# 140709_AriloTX_REV2_1_0.net
KiCad netlist of a schematic drawn in EAGLE
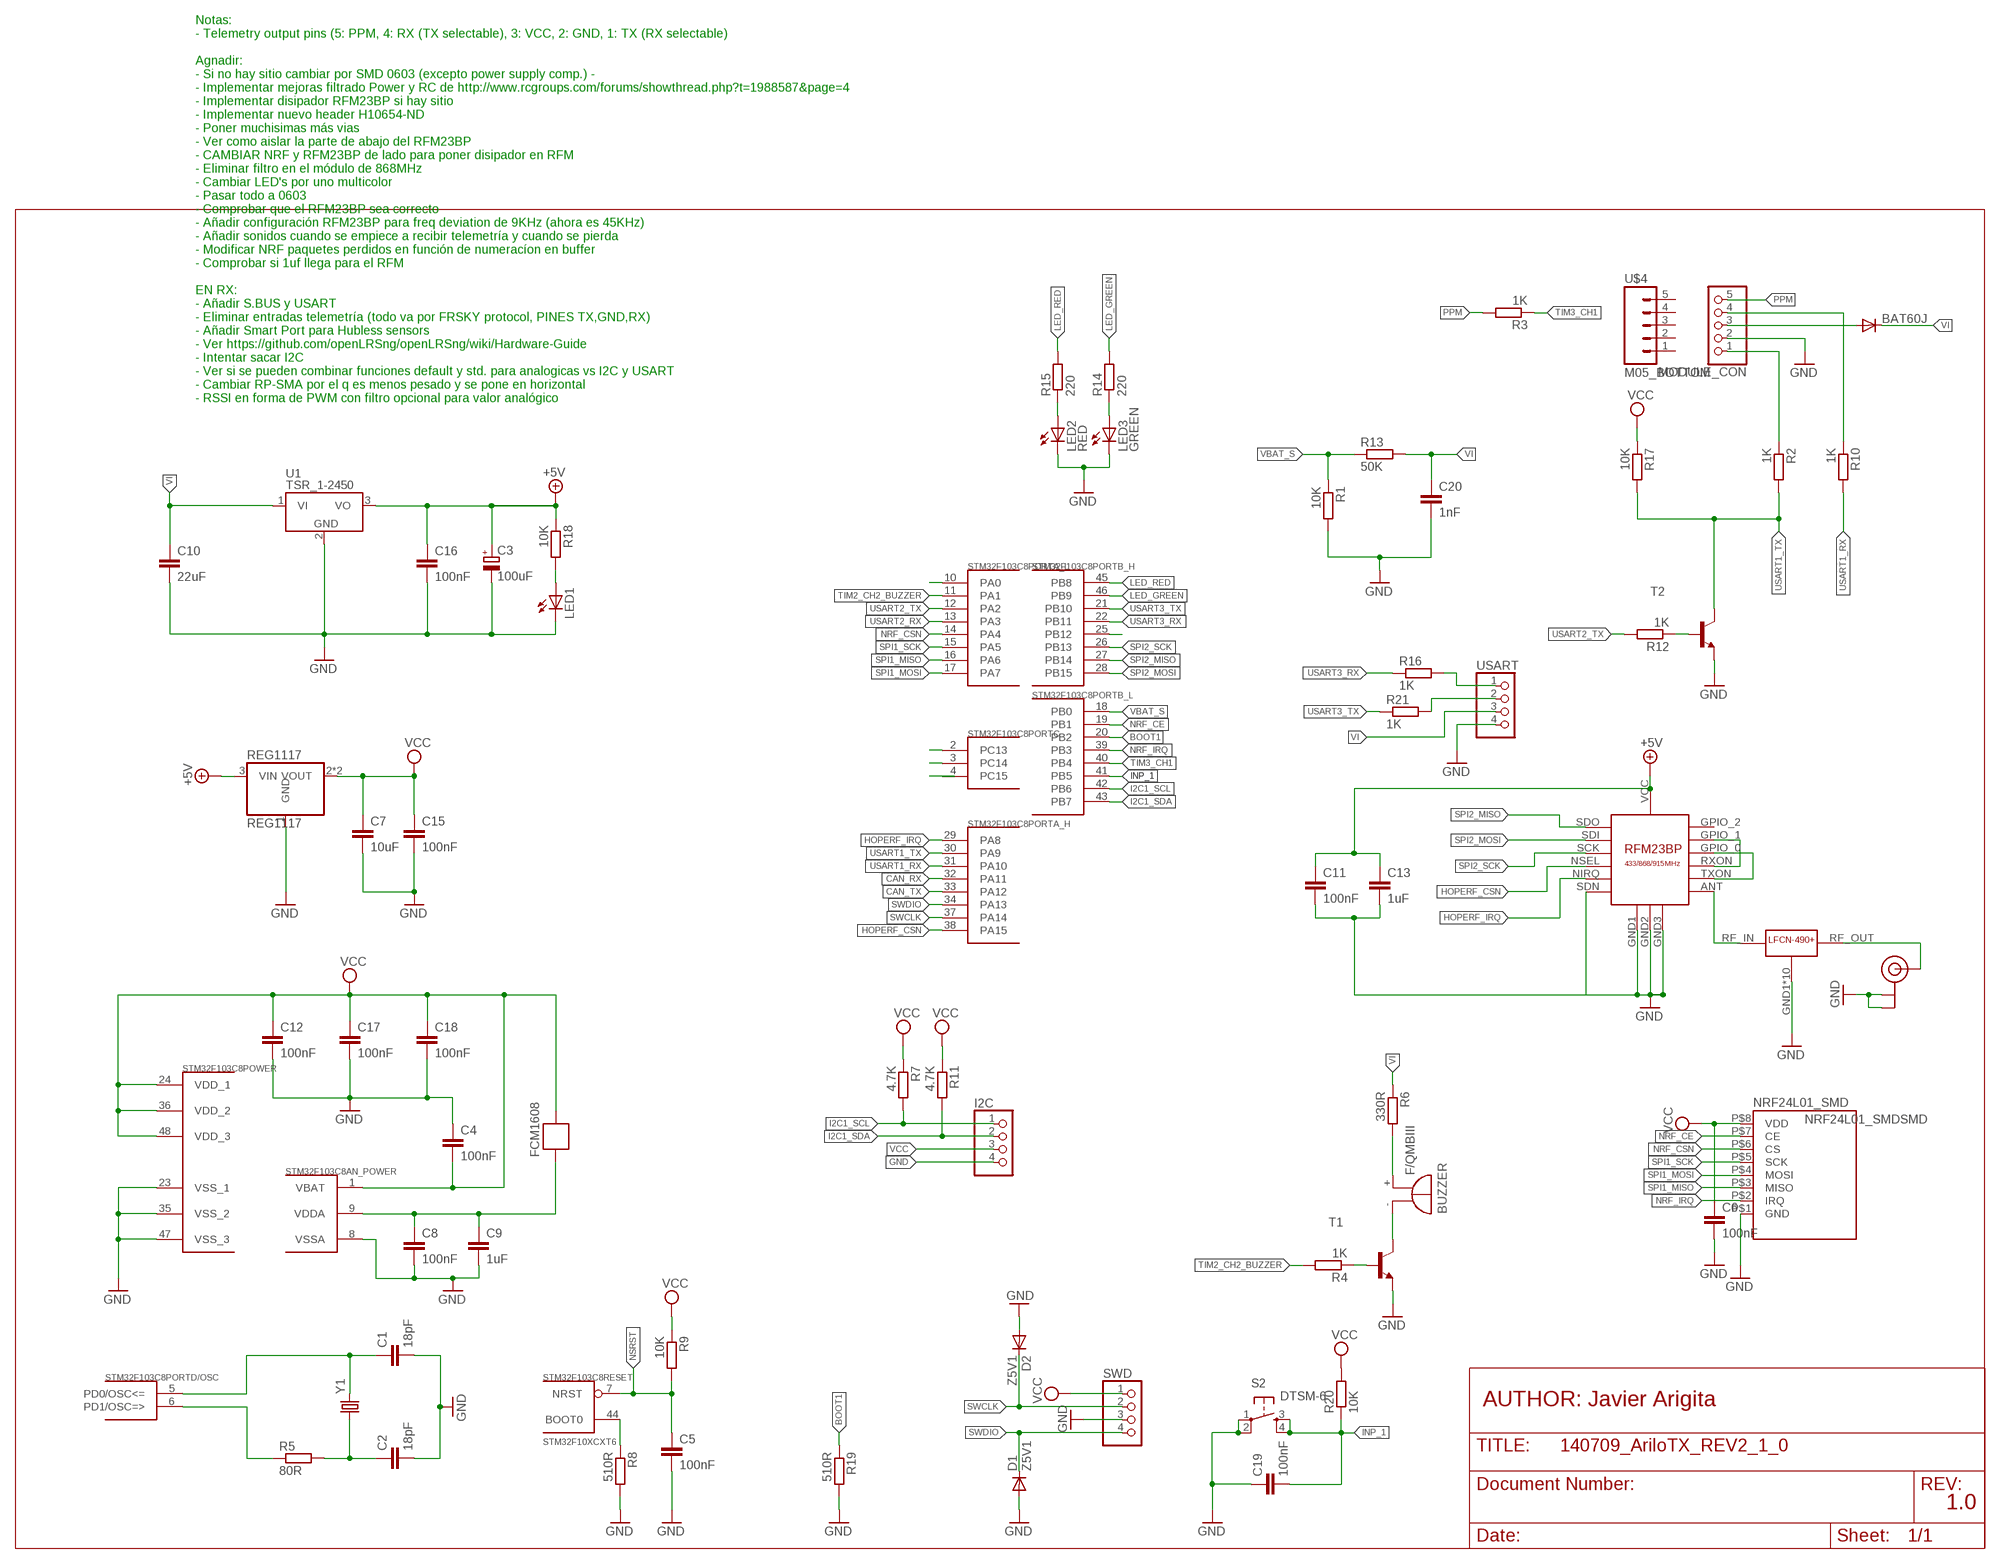
[diagram p0: schematic, sheet 1]

(export (version "E")
  (design (tool "Eeschema 10.0.6"))
  (components
    (comp (ref "BAT60J")
      (value "DIODE-SOD323-R")
      (footprint "eagle-import:SOD323-R")
      (libsource (lib "eagle-import") (part "DIODE-SOD323-R"))
    )
    (comp (ref "BUZZER")
      (value "F/QMBIII")
      (footprint "eagle-import:F_QMBIII")
      (libsource (lib "eagle-import") (part "F/QMBIII"))
    )
    (comp (ref "C1")
      (value "18pF")
      (footprint "eagle-import:C0603")
      (libsource (lib "eagle-import") (part "C-EUC0603"))
    )
    (comp (ref "C2")
      (value "18pF")
      (footprint "eagle-import:C0603")
      (libsource (lib "eagle-import") (part "C-EUC0603"))
    )
    (comp (ref "C3")
      (value "100uF")
      (footprint "eagle-import:SMC_B")
      (libsource (lib "eagle-import") (part "CPOL-EUSMCB"))
    )
    (comp (ref "C4")
      (value "100nF")
      (footprint "eagle-import:C0603")
      (libsource (lib "eagle-import") (part "C-EUC0603"))
    )
    (comp (ref "C5")
      (value "100nF")
      (footprint "eagle-import:C0603")
      (libsource (lib "eagle-import") (part "C-EUC0603"))
    )
    (comp (ref "C6")
      (value "100nF")
      (footprint "eagle-import:C0603")
      (libsource (lib "eagle-import") (part "C-EUC0603"))
    )
    (comp (ref "C7")
      (value "10uF")
      (footprint "eagle-import:C0805")
      (libsource (lib "eagle-import") (part "C-EUC0805"))
    )
    (comp (ref "C8")
      (value "100nF")
      (footprint "eagle-import:C0603")
      (libsource (lib "eagle-import") (part "C-EUC0603"))
    )
    (comp (ref "C9")
      (value "1uF")
      (footprint "eagle-import:C0603")
      (libsource (lib "eagle-import") (part "C-EUC0603"))
    )
    (comp (ref "C10")
      (value "22uF")
      (footprint "eagle-import:C3216")
      (libsource (lib "eagle-import") (part "resistor_C-EUC3216"))
    )
    (comp (ref "C11")
      (value "100nF")
      (footprint "eagle-import:C0603")
      (libsource (lib "eagle-import") (part "C-EUC0603"))
    )
    (comp (ref "C12")
      (value "100nF")
      (footprint "eagle-import:C0603")
      (libsource (lib "eagle-import") (part "C-EUC0603"))
    )
    (comp (ref "C13")
      (value "1uF")
      (footprint "eagle-import:C0603")
      (libsource (lib "eagle-import") (part "C-EUC0603"))
    )
    (comp (ref "C15")
      (value "100nF")
      (footprint "eagle-import:C0603")
      (libsource (lib "eagle-import") (part "C-EUC0603"))
    )
    (comp (ref "C16")
      (value "100nF")
      (footprint "eagle-import:C0603")
      (libsource (lib "eagle-import") (part "C-EUC0603"))
    )
    (comp (ref "C17")
      (value "100nF")
      (footprint "eagle-import:C0603")
      (libsource (lib "eagle-import") (part "C-EUC0603"))
    )
    (comp (ref "C18")
      (value "100nF")
      (footprint "eagle-import:C0603")
      (libsource (lib "eagle-import") (part "C-EUC0603"))
    )
    (comp (ref "C19")
      (value "100nF")
      (footprint "eagle-import:C0603")
      (libsource (lib "eagle-import") (part "C-EUC0603"))
    )
    (comp (ref "C20")
      (value "1nF")
      (footprint "eagle-import:C0603")
      (libsource (lib "eagle-import") (part "C-EUC0603"))
    )
    (comp (ref "D1")
      (value "Z5V1")
      (footprint "eagle-import:SOD323-R")
      (libsource (lib "eagle-import") (part "DIODE-SOD323-R"))
    )
    (comp (ref "D2")
      (value "Z5V1")
      (footprint "eagle-import:SOD323-R")
      (libsource (lib "eagle-import") (part "DIODE-SOD323-R"))
    )
    (comp (ref "FCM1608")
      (value "FERRITE-BEAD")
      (footprint "eagle-import:R0603")
      (libsource (lib "eagle-import") (part "FERRITE-BEAD"))
    )
    (comp (ref "I2C")
      (value "PINHD-1X4")
      (footprint "eagle-import:1X04")
      (libsource (lib "eagle-import") (part "PINHD-1X4"))
    )
    (comp (ref "LED1")
      (value "LEDCHIP-LED0603")
      (footprint "eagle-import:CHIP-LED0603")
      (libsource (lib "eagle-import") (part "LEDCHIP-LED0603"))
    )
    (comp (ref "LED2")
      (value "RED")
      (footprint "eagle-import:CHIP-LED0603")
      (libsource (lib "eagle-import") (part "LEDCHIP-LED0603"))
    )
    (comp (ref "LED3")
      (value "GREEN")
      (footprint "eagle-import:CHIP-LED0603")
      (libsource (lib "eagle-import") (part "LEDCHIP-LED0603"))
    )
    (comp (ref "MODULE_CON")
      (value "PINHD-1X5")
      (footprint "eagle-import:1X05")
      (libsource (lib "eagle-import") (part "PINHD-1X5"))
    )
    (comp (ref "NRF24L01_SMD")
      (value "NRF24L01_SMDSMD")
      (footprint "eagle-import:NRF24L01_SMD")
      (libsource (lib "eagle-import") (part "NRF24L01_SMDSMD"))
    )
    (comp (ref "R1")
      (value "10K")
      (footprint "eagle-import:R0603")
      (libsource (lib "eagle-import") (part "R-EU_R0603"))
    )
    (comp (ref "R2")
      (value "1K")
      (footprint "eagle-import:R0603")
      (libsource (lib "eagle-import") (part "R-EU_R0603"))
    )
    (comp (ref "R3")
      (value "1K")
      (footprint "eagle-import:R0603")
      (libsource (lib "eagle-import") (part "R-EU_R0603"))
    )
    (comp (ref "R4")
      (value "1K")
      (footprint "eagle-import:R0603")
      (libsource (lib "eagle-import") (part "R-EU_R0603"))
    )
    (comp (ref "R5")
      (value "80R")
      (footprint "eagle-import:R0603")
      (libsource (lib "eagle-import") (part "R-EU_R0603"))
    )
    (comp (ref "R6")
      (value "330R")
      (footprint "eagle-import:R0603")
      (libsource (lib "eagle-import") (part "R-EU_R0603"))
    )
    (comp (ref "R7")
      (value "4.7K")
      (footprint "eagle-import:R0603")
      (libsource (lib "eagle-import") (part "R-EU_R0603"))
    )
    (comp (ref "R8")
      (value "510R")
      (footprint "eagle-import:R0603")
      (libsource (lib "eagle-import") (part "R-EU_R0603"))
    )
    (comp (ref "R9")
      (value "10K")
      (footprint "eagle-import:R0603")
      (libsource (lib "eagle-import") (part "R-EU_R0603"))
    )
    (comp (ref "R10")
      (value "1K")
      (footprint "eagle-import:R0603")
      (libsource (lib "eagle-import") (part "R-EU_R0603"))
    )
    (comp (ref "R11")
      (value "4.7K")
      (footprint "eagle-import:R0603")
      (libsource (lib "eagle-import") (part "R-EU_R0603"))
    )
    (comp (ref "R12")
      (value "1K")
      (footprint "eagle-import:R0603")
      (libsource (lib "eagle-import") (part "R-EU_R0603"))
    )
    (comp (ref "R13")
      (value "50K")
      (footprint "eagle-import:R0603")
      (libsource (lib "eagle-import") (part "R-EU_R0603"))
    )
    (comp (ref "R14")
      (value "220")
      (footprint "eagle-import:R0603")
      (libsource (lib "eagle-import") (part "R-EU_R0603"))
    )
    (comp (ref "R15")
      (value "220")
      (footprint "eagle-import:R0603")
      (libsource (lib "eagle-import") (part "R-EU_R0603"))
    )
    (comp (ref "R16")
      (value "1K")
      (footprint "eagle-import:R0603")
      (libsource (lib "eagle-import") (part "R-EU_R0603"))
    )
    (comp (ref "R17")
      (value "10K")
      (footprint "eagle-import:R0603")
      (libsource (lib "eagle-import") (part "R-EU_R0603"))
    )
    (comp (ref "R18")
      (value "10K")
      (footprint "eagle-import:R0603")
      (libsource (lib "eagle-import") (part "R-EU_R0603"))
    )
    (comp (ref "R19")
      (value "510R")
      (footprint "eagle-import:R0603")
      (libsource (lib "eagle-import") (part "R-EU_R0603"))
    )
    (comp (ref "R20")
      (value "10K")
      (footprint "eagle-import:R0603")
      (libsource (lib "eagle-import") (part "R-EU_R0603"))
    )
    (comp (ref "R21")
      (value "1K")
      (footprint "eagle-import:R0603")
      (libsource (lib "eagle-import") (part "R-EU_R0603"))
    )
    (comp (ref "REG1117")
      (value "REG1117")
      (footprint "eagle-import:SOT223")
      (libsource (lib "eagle-import") (part "REG1117"))
    )
    (comp (ref "S2")
      (value "DTSM-6")
      (footprint "eagle-import:DTSM-6")
      (libsource (lib "eagle-import") (part "DTSM-6"))
    )
    (comp (ref "STM32F103C8")
      (value "STM32F10XCXT6")
      (footprint "eagle-import:TQFP48")
      (libsource (lib "eagle-import") (part "STM32F10XCXT6"))
    )
    (comp (ref "SWD")
      (value "PINHD-1X4")
      (footprint "eagle-import:1X04")
      (libsource (lib "eagle-import") (part "PINHD-1X4"))
    )
    (comp (ref "T1")
      (value "BC848-NPN-SOT23-BEC")
      (footprint "eagle-import:SOT23-BEC")
      (libsource (lib "eagle-import") (part "-NPN-SOT23-BECBC848"))
    )
    (comp (ref "T2")
      (value "BC848-NPN-SOT23-BEC")
      (footprint "eagle-import:SOT23-BEC")
      (libsource (lib "eagle-import") (part "-NPN-SOT23-BECBC848"))
    )
    (comp (ref "U$1")
      (value "RFM23BP")
      (footprint "eagle-import:RFM23BP")
      (libsource (lib "eagle-import") (part "RFM23BP"))
    )
    (comp (ref "U$2")
      (value "LFCN490+")
      (footprint "eagle-import:LFCN490+")
      (libsource (lib "eagle-import") (part "LFCN490+"))
    )
    (comp (ref "U$3")
      (value "U.FL")
      (footprint "eagle-import:U.FL")
      (libsource (lib "eagle-import") (part "U.FL"))
    )
    (comp (ref "U$4")
      (value "M05_BOTTOM")
      (footprint "eagle-import:M05_BOTTOM")
      (libsource (lib "eagle-import") (part "M05_BOTTOM"))
    )
    (comp (ref "U1")
      (value "TSR_1-2450")
      (footprint "eagle-import:TSR-1")
      (libsource (lib "eagle-import") (part "TSR_1-2450"))
    )
    (comp (ref "USART")
      (value "PINHD-1X4")
      (footprint "eagle-import:1X04")
      (libsource (lib "eagle-import") (part "PINHD-1X4"))
    )
    (comp (ref "Y1")
      (value "CRYSTAL5X3")
      (footprint "eagle-import:CRYSTAL-SMD-5X3")
      (libsource (lib "eagle-import") (part "CRYSTAL5X3"))
    )
  )
  (nets
    (net (code "1") (name "+5V") (class "Default")
      (node (ref "C11") (pin "1") (pinfunction "1_1") (pintype "passive"))
      (node (ref "C13") (pin "1") (pinfunction "1_1") (pintype "passive"))
      (node (ref "C16") (pin "1") (pinfunction "1_1") (pintype "passive"))
      (node (ref "C3") (pin "+") (pinfunction "+_+") (pintype "passive"))
      (node (ref "R18") (pin "1") (pinfunction "1_1") (pintype "passive"))
      (node (ref "REG1117") (pin "3") (pinfunction "VIN_3") (pintype "input"))
      (node (ref "U$1") (pin "VCC") (pinfunction "VCC_VCC") (pintype "power_in"))
      (node (ref "U1") (pin "3") (pinfunction "VO_3") (pintype "power_in"))
    )
    (net (code "2") (name "BOOT1") (class "Default")
      (node (ref "R19") (pin "1") (pinfunction "1_1") (pintype "passive"))
      (node (ref "STM32F103C8") (pin "20") (pinfunction "PB2_20") (pintype "bidirectional"))
    )
    (net (code "3") (name "CAN_RX") (class "Default")
      (node (ref "STM32F103C8") (pin "32") (pinfunction "PA11_32") (pintype "bidirectional"))
    )
    (net (code "4") (name "CAN_TX") (class "Default")
      (node (ref "STM32F103C8") (pin "33") (pinfunction "PA12_33") (pintype "bidirectional"))
    )
    (net (code "5") (name "GND") (class "Default")
      (node (ref "C1") (pin "2") (pinfunction "2_2") (pintype "passive"))
      (node (ref "C10") (pin "2") (pinfunction "2_2") (pintype "passive"))
      (node (ref "C11") (pin "2") (pinfunction "2_2") (pintype "passive"))
      (node (ref "C12") (pin "2") (pinfunction "2_2") (pintype "passive"))
      (node (ref "C13") (pin "2") (pinfunction "2_2") (pintype "passive"))
      (node (ref "C15") (pin "2") (pinfunction "2_2") (pintype "passive"))
      (node (ref "C16") (pin "2") (pinfunction "2_2") (pintype "passive"))
      (node (ref "C17") (pin "2") (pinfunction "2_2") (pintype "passive"))
      (node (ref "C18") (pin "2") (pinfunction "2_2") (pintype "passive"))
      (node (ref "C19") (pin "1") (pinfunction "1_1") (pintype "passive"))
      (node (ref "C2") (pin "2") (pinfunction "2_2") (pintype "passive"))
      (node (ref "C20") (pin "2") (pinfunction "2_2") (pintype "passive"))
      (node (ref "C3") (pin "-") (pinfunction "-_-") (pintype "passive"))
      (node (ref "C4") (pin "1") (pinfunction "1_1") (pintype "passive"))
      (node (ref "C5") (pin "2") (pinfunction "2_2") (pintype "passive"))
      (node (ref "C6") (pin "2") (pinfunction "2_2") (pintype "passive"))
      (node (ref "C7") (pin "2") (pinfunction "2_2") (pintype "passive"))
      (node (ref "C8") (pin "2") (pinfunction "2_2") (pintype "passive"))
      (node (ref "C9") (pin "2") (pinfunction "2_2") (pintype "passive"))
      (node (ref "D1") (pin "A") (pinfunction "A_A") (pintype "passive"))
      (node (ref "D2") (pin "A") (pinfunction "A_A") (pintype "passive"))
      (node (ref "I2C") (pin "4") (pinfunction "4_4") (pintype "passive"))
      (node (ref "LED1") (pin "C") (pinfunction "C_C") (pintype "passive"))
      (node (ref "LED2") (pin "C") (pinfunction "C_C") (pintype "passive"))
      (node (ref "LED3") (pin "C") (pinfunction "C_C") (pintype "passive"))
      (node (ref "MODULE_CON") (pin "2") (pinfunction "2_2") (pintype "passive"))
      (node (ref "NRF24L01_SMD") (pin "P$1") (pinfunction "GND_P$1") (pintype "power_in"))
      (node (ref "R1") (pin "2") (pinfunction "2_2") (pintype "passive"))
      (node (ref "R19") (pin "2") (pinfunction "2_2") (pintype "passive"))
      (node (ref "R8") (pin "2") (pinfunction "2_2") (pintype "passive"))
      (node (ref "REG1117") (pin "1") (pinfunction "GND_1") (pintype "power_in"))
      (node (ref "S2") (pin "1") (pinfunction "1_1") (pintype "passive"))
      (node (ref "S2") (pin "2") (pinfunction "2_2") (pintype "passive"))
      (node (ref "STM32F103C8") (pin "23") (pinfunction "VSS_1_23") (pintype "power_in"))
      (node (ref "STM32F103C8") (pin "35") (pinfunction "VSS_2_35") (pintype "power_in"))
      (node (ref "STM32F103C8") (pin "47") (pinfunction "VSS_3_47") (pintype "power_in"))
      (node (ref "STM32F103C8") (pin "8") (pinfunction "VSSA_8") (pintype "power_in"))
      (node (ref "SWD") (pin "3") (pinfunction "3_3") (pintype "passive"))
      (node (ref "T1") (pin "E") (pinfunction "E_E") (pintype "passive"))
      (node (ref "T2") (pin "E") (pinfunction "E_E") (pintype "passive"))
      (node (ref "U$1") (pin "GND1") (pinfunction "GND1_GND1") (pintype "power_in"))
      (node (ref "U$1") (pin "GND2") (pinfunction "GND2_GND2") (pintype "power_in"))
      (node (ref "U$1") (pin "GND3") (pinfunction "GND3_GND3") (pintype "power_in"))
      (node (ref "U$1") (pin "SDN") (pinfunction "SDN_SDN") (pintype "bidirectional"))
      (node (ref "U$2") (pin "GND1") (pinfunction "GND_GND1") (pintype "bidirectional"))
      (node (ref "U$2") (pin "GND10") (pinfunction "GND_GND10") (pintype "bidirectional"))
      (node (ref "U$2") (pin "GND2") (pinfunction "GND_GND2") (pintype "bidirectional"))
      (node (ref "U$2") (pin "GND3") (pinfunction "GND_GND3") (pintype "bidirectional"))
      (node (ref "U$2") (pin "GND4") (pinfunction "GND_GND4") (pintype "bidirectional"))
      (node (ref "U$2") (pin "GND5") (pinfunction "GND_GND5") (pintype "bidirectional"))
      (node (ref "U$2") (pin "GND6") (pinfunction "GND_GND6") (pintype "bidirectional"))
      (node (ref "U$2") (pin "GND7") (pinfunction "GND_GND7") (pintype "bidirectional"))
      (node (ref "U$2") (pin "GND8") (pinfunction "GND_GND8") (pintype "bidirectional"))
      (node (ref "U$2") (pin "GND9") (pinfunction "GND_GND9") (pintype "bidirectional"))
      (node (ref "U$3") (pin "P$1") (pinfunction "GND_P$1") (pintype "bidirectional"))
      (node (ref "U$3") (pin "P$2") (pinfunction "GND_P$2") (pintype "bidirectional"))
      (node (ref "U1") (pin "2") (pinfunction "GND_2") (pintype "power_in"))
      (node (ref "USART") (pin "4") (pinfunction "4_4") (pintype "passive"))
    )
    (net (code "6") (name "HOPERF_CSN") (class "Default")
      (node (ref "STM32F103C8") (pin "38") (pinfunction "PA15_38") (pintype "bidirectional"))
      (node (ref "U$1") (pin "NSEL") (pinfunction "NSEL_NSEL") (pintype "bidirectional"))
    )
    (net (code "7") (name "HOPERF_IRQ") (class "Default")
      (node (ref "STM32F103C8") (pin "29") (pinfunction "PA8_29") (pintype "bidirectional"))
      (node (ref "U$1") (pin "NIRQ") (pinfunction "NIRQ_NIRQ") (pintype "bidirectional"))
    )
    (net (code "8") (name "I2C1_SCL") (class "Default")
      (node (ref "I2C") (pin "1") (pinfunction "1_1") (pintype "passive"))
      (node (ref "R7") (pin "2") (pinfunction "2_2") (pintype "passive"))
      (node (ref "STM32F103C8") (pin "42") (pinfunction "PB6_42") (pintype "bidirectional"))
    )
    (net (code "9") (name "I2C1_SDA") (class "Default")
      (node (ref "I2C") (pin "2") (pinfunction "2_2") (pintype "passive"))
      (node (ref "R11") (pin "2") (pinfunction "2_2") (pintype "passive"))
      (node (ref "STM32F103C8") (pin "43") (pinfunction "PB7_43") (pintype "bidirectional"))
    )
    (net (code "10") (name "INP_1") (class "Default")
      (node (ref "C19") (pin "2") (pinfunction "2_2") (pintype "passive"))
      (node (ref "R20") (pin "1") (pinfunction "1_1") (pintype "passive"))
      (node (ref "S2") (pin "3") (pinfunction "3_3") (pintype "passive"))
      (node (ref "S2") (pin "4") (pinfunction "4_4") (pintype "passive"))
      (node (ref "STM32F103C8") (pin "41") (pinfunction "PB5_41") (pintype "bidirectional"))
    )
    (net (code "11") (name "LED_GREEN") (class "Default")
      (node (ref "R14") (pin "2") (pinfunction "2_2") (pintype "passive"))
      (node (ref "STM32F103C8") (pin "46") (pinfunction "PB9_46") (pintype "bidirectional"))
    )
    (net (code "12") (name "LED_RED") (class "Default")
      (node (ref "R15") (pin "2") (pinfunction "2_2") (pintype "passive"))
      (node (ref "STM32F103C8") (pin "45") (pinfunction "PB8_45") (pintype "bidirectional"))
    )
    (net (code "13") (name "NRF_CE") (class "Default")
      (node (ref "NRF24L01_SMD") (pin "P$7") (pinfunction "CE_P$7") (pintype "input"))
      (node (ref "STM32F103C8") (pin "19") (pinfunction "PB1_19") (pintype "bidirectional"))
    )
    (net (code "14") (name "NRF_CSN") (class "Default")
      (node (ref "NRF24L01_SMD") (pin "P$6") (pinfunction "CS_P$6") (pintype "input"))
      (node (ref "STM32F103C8") (pin "14") (pinfunction "PA4_14") (pintype "bidirectional"))
    )
    (net (code "15") (name "NRF_IRQ") (class "Default")
      (node (ref "NRF24L01_SMD") (pin "P$2") (pinfunction "IRQ_P$2") (pintype "output"))
      (node (ref "STM32F103C8") (pin "39") (pinfunction "PB3_39") (pintype "bidirectional"))
    )
    (net (code "16") (name "NSRST") (class "Default")
      (node (ref "C5") (pin "1") (pinfunction "1_1") (pintype "passive"))
      (node (ref "R9") (pin "2") (pinfunction "2_2") (pintype "passive"))
      (node (ref "STM32F103C8") (pin "7") (pinfunction "NRST_7") (pintype "input"))
    )
    (net (code "17") (name "Net-(BAT60J-PadA)") (class "Default")
      (node (ref "BAT60J") (pin "A") (pinfunction "A_A") (pintype "passive"))
      (node (ref "MODULE_CON") (pin "3") (pinfunction "3_3") (pintype "passive"))
    )
    (net (code "18") (name "Net-(BUZZER-+)") (class "Default")
      (node (ref "BUZZER") (pin "-") (pinfunction "+_-") (pintype "passive"))
      (node (ref "T1") (pin "C") (pinfunction "C_C") (pintype "passive"))
    )
    (net (code "19") (name "Net-(BUZZER--)") (class "Default")
      (node (ref "BUZZER") (pin "+") (pinfunction "-_+") (pintype "passive"))
      (node (ref "R6") (pin "2") (pinfunction "2_2") (pintype "passive"))
    )
    (net (code "20") (name "Net-(C2-Pad1)") (class "Default")
      (node (ref "C2") (pin "1") (pinfunction "1_1") (pintype "passive"))
      (node (ref "R5") (pin "2") (pinfunction "2_2") (pintype "passive"))
      (node (ref "Y1") (pin "1") (pinfunction "1_1") (pintype "passive"))
    )
    (net (code "21") (name "Net-(FCM1608-P$2)") (class "Default")
      (node (ref "C8") (pin "1") (pinfunction "1_1") (pintype "passive"))
      (node (ref "C9") (pin "1") (pinfunction "1_1") (pintype "passive"))
      (node (ref "FCM1608") (pin "2") (pinfunction "P$2_2") (pintype "bidirectional"))
      (node (ref "STM32F103C8") (pin "9") (pinfunction "VDDA_9") (pintype "power_in"))
    )
    (net (code "22") (name "Net-(LED1-PadA)") (class "Default")
      (node (ref "LED1") (pin "A") (pinfunction "A_A") (pintype "passive"))
      (node (ref "R18") (pin "2") (pinfunction "2_2") (pintype "passive"))
    )
    (net (code "23") (name "Net-(LED2-PadA)") (class "Default")
      (node (ref "LED2") (pin "A") (pinfunction "A_A") (pintype "passive"))
      (node (ref "R15") (pin "1") (pinfunction "1_1") (pintype "passive"))
    )
    (net (code "24") (name "Net-(LED3-PadA)") (class "Default")
      (node (ref "LED3") (pin "A") (pinfunction "A_A") (pintype "passive"))
      (node (ref "R14") (pin "1") (pinfunction "1_1") (pintype "passive"))
    )
    (net (code "25") (name "Net-(MODULE_CON-Pad1)") (class "Default")
      (node (ref "MODULE_CON") (pin "1") (pinfunction "1_1") (pintype "passive"))
      (node (ref "R2") (pin "1") (pinfunction "1_1") (pintype "passive"))
    )
    (net (code "26") (name "Net-(MODULE_CON-Pad4)") (class "Default")
      (node (ref "MODULE_CON") (pin "4") (pinfunction "4_4") (pintype "passive"))
      (node (ref "R10") (pin "1") (pinfunction "1_1") (pintype "passive"))
    )
    (net (code "27") (name "Net-(R4-Pad1)") (class "Default")
      (node (ref "R4") (pin "1") (pinfunction "1_1") (pintype "passive"))
      (node (ref "T1") (pin "B") (pinfunction "B_B") (pintype "passive"))
    )
    (net (code "28") (name "Net-(R12-Pad1)") (class "Default")
      (node (ref "R12") (pin "1") (pinfunction "1_1") (pintype "passive"))
      (node (ref "T2") (pin "B") (pinfunction "B_B") (pintype "passive"))
    )
    (net (code "29") (name "Net-(R16-Pad2)") (class "Default")
      (node (ref "R16") (pin "2") (pinfunction "2_2") (pintype "passive"))
      (node (ref "USART") (pin "1") (pinfunction "1_1") (pintype "passive"))
    )
    (net (code "30") (name "Net-(R21-Pad2)") (class "Default")
      (node (ref "R21") (pin "2") (pinfunction "2_2") (pintype "passive"))
      (node (ref "USART") (pin "2") (pinfunction "2_2") (pintype "passive"))
    )
    (net (code "31") (name "Net-(STM32F103C8G-PD0{slash}OSC<=)") (class "Default")
      (node (ref "C1") (pin "1") (pinfunction "1_1") (pintype "passive"))
      (node (ref "STM32F103C8") (pin "5") (pinfunction "PD0/OSC<=_5") (pintype "bidirectional"))
      (node (ref "Y1") (pin "3") (pinfunction "2_3") (pintype "passive"))
    )
    (net (code "32") (name "Net-(STM32F103C8G-PD1{slash}OSC=>)") (class "Default")
      (node (ref "R5") (pin "1") (pinfunction "1_1") (pintype "passive"))
      (node (ref "STM32F103C8") (pin "6") (pinfunction "PD1/OSC=>_6") (pintype "bidirectional"))
    )
    (net (code "33") (name "Net-(STM32F103C8I-BOOT0)") (class "Default")
      (node (ref "R8") (pin "1") (pinfunction "1_1") (pintype "passive"))
      (node (ref "STM32F103C8") (pin "44") (pinfunction "BOOT0_44") (pintype "input"))
    )
    (net (code "34") (name "Net-(U$1-PadGPIO_0)") (class "Default")
      (node (ref "U$1") (pin "GPIO_0") (pinfunction "GPIO_0_GPIO_0") (pintype "bidirectional"))
      (node (ref "U$1") (pin "TXON") (pinfunction "TXON_TXON") (pintype "bidirectional"))
    )
    (net (code "35") (name "Net-(U$1-PadGPIO_1)") (class "Default")
      (node (ref "U$1") (pin "GPIO_1") (pinfunction "GPIO_1_GPIO_1") (pintype "bidirectional"))
      (node (ref "U$1") (pin "RXON") (pinfunction "RXON_RXON") (pintype "bidirectional"))
    )
    (net (code "36") (name "Net-(U$2-RF_INP)") (class "Default")
      (node (ref "U$1") (pin "ANT") (pinfunction "ANT_ANT") (pintype "bidirectional"))
      (node (ref "U$2") (pin "RF_IN") (pinfunction "RF_INP_RF_IN") (pintype "bidirectional"))
    )
    (net (code "37") (name "Net-(U$2-RF_OUTP)") (class "Default")
      (node (ref "U$2") (pin "RF_OUT") (pinfunction "RF_OUTP_RF_OUT") (pintype "bidirectional"))
      (node (ref "U$3") (pin "P$3") (pinfunction "SIGNAL_P$3") (pintype "bidirectional"))
    )
    (net (code "38") (name "PPM") (class "Default")
      (node (ref "MODULE_CON") (pin "5") (pinfunction "5_5") (pintype "passive"))
      (node (ref "R3") (pin "2") (pinfunction "2_2") (pintype "passive"))
    )
    (net (code "39") (name "SPI1_MISO") (class "Default")
      (node (ref "NRF24L01_SMD") (pin "P$3") (pinfunction "MISO_P$3") (pintype "output"))
      (node (ref "STM32F103C8") (pin "16") (pinfunction "PA6_16") (pintype "bidirectional"))
    )
    (net (code "40") (name "SPI1_MOSI") (class "Default")
      (node (ref "NRF24L01_SMD") (pin "P$4") (pinfunction "MOSI_P$4") (pintype "input"))
      (node (ref "STM32F103C8") (pin "17") (pinfunction "PA7_17") (pintype "bidirectional"))
    )
    (net (code "41") (name "SPI1_SCK") (class "Default")
      (node (ref "NRF24L01_SMD") (pin "P$5") (pinfunction "SCK_P$5") (pintype "input"))
      (node (ref "STM32F103C8") (pin "15") (pinfunction "PA5_15") (pintype "bidirectional"))
    )
    (net (code "42") (name "SPI2_MISO") (class "Default")
      (node (ref "STM32F103C8") (pin "27") (pinfunction "PB14_27") (pintype "bidirectional"))
      (node (ref "U$1") (pin "SDO") (pinfunction "SDO_SDO") (pintype "bidirectional"))
    )
    (net (code "43") (name "SPI2_MOSI") (class "Default")
      (node (ref "STM32F103C8") (pin "28") (pinfunction "PB15_28") (pintype "bidirectional"))
      (node (ref "U$1") (pin "SDI") (pinfunction "SDI_SDI") (pintype "bidirectional"))
    )
    (net (code "44") (name "SPI2_SCK") (class "Default")
      (node (ref "STM32F103C8") (pin "26") (pinfunction "PB13_26") (pintype "bidirectional"))
      (node (ref "U$1") (pin "SCK") (pinfunction "SCK_SCK") (pintype "bidirectional"))
    )
    (net (code "45") (name "SWCLK") (class "Default")
      (node (ref "D2") (pin "C") (pinfunction "C_C") (pintype "passive"))
      (node (ref "STM32F103C8") (pin "37") (pinfunction "PA14_37") (pintype "bidirectional"))
      (node (ref "SWD") (pin "2") (pinfunction "2_2") (pintype "passive"))
    )
    (net (code "46") (name "SWDIO") (class "Default")
      (node (ref "D1") (pin "C") (pinfunction "C_C") (pintype "passive"))
      (node (ref "STM32F103C8") (pin "34") (pinfunction "PA13_34") (pintype "bidirectional"))
      (node (ref "SWD") (pin "4") (pinfunction "4_4") (pintype "passive"))
    )
    (net (code "47") (name "TIM2_CH2_BUZZER") (class "Default")
      (node (ref "R4") (pin "2") (pinfunction "2_2") (pintype "passive"))
      (node (ref "STM32F103C8") (pin "11") (pinfunction "PA1_11") (pintype "bidirectional"))
    )
    (net (code "48") (name "TIM3_CH1") (class "Default")
      (node (ref "R3") (pin "1") (pinfunction "1_1") (pintype "passive"))
      (node (ref "STM32F103C8") (pin "40") (pinfunction "PB4_40") (pintype "bidirectional"))
    )
    (net (code "49") (name "USART1_RX") (class "Default")
      (node (ref "R10") (pin "2") (pinfunction "2_2") (pintype "passive"))
      (node (ref "STM32F103C8") (pin "31") (pinfunction "PA10_31") (pintype "bidirectional"))
    )
    (net (code "50") (name "USART1_TX") (class "Default")
      (node (ref "R17") (pin "2") (pinfunction "2_2") (pintype "passive"))
      (node (ref "R2") (pin "2") (pinfunction "2_2") (pintype "passive"))
      (node (ref "STM32F103C8") (pin "30") (pinfunction "PA9_30") (pintype "bidirectional"))
      (node (ref "T2") (pin "C") (pinfunction "C_C") (pintype "passive"))
    )
    (net (code "51") (name "USART2_RX") (class "Default")
      (node (ref "STM32F103C8") (pin "13") (pinfunction "PA3_13") (pintype "bidirectional"))
    )
    (net (code "52") (name "USART2_TX") (class "Default")
      (node (ref "R12") (pin "2") (pinfunction "2_2") (pintype "passive"))
      (node (ref "STM32F103C8") (pin "12") (pinfunction "PA2_12") (pintype "bidirectional"))
    )
    (net (code "53") (name "USART3_RX") (class "Default")
      (node (ref "R16") (pin "1") (pinfunction "1_1") (pintype "passive"))
      (node (ref "STM32F103C8") (pin "22") (pinfunction "PB11_22") (pintype "bidirectional"))
    )
    (net (code "54") (name "USART3_TX") (class "Default")
      (node (ref "R21") (pin "1") (pinfunction "1_1") (pintype "passive"))
      (node (ref "STM32F103C8") (pin "21") (pinfunction "PB10_21") (pintype "bidirectional"))
    )
    (net (code "55") (name "VBAT_S") (class "Default")
      (node (ref "R1") (pin "1") (pinfunction "1_1") (pintype "passive"))
      (node (ref "R13") (pin "1") (pinfunction "1_1") (pintype "passive"))
      (node (ref "STM32F103C8") (pin "18") (pinfunction "PB0_18") (pintype "bidirectional"))
    )
    (net (code "56") (name "VCC") (class "Default")
      (node (ref "C12") (pin "1") (pinfunction "1_1") (pintype "passive"))
      (node (ref "C15") (pin "1") (pinfunction "1_1") (pintype "passive"))
      (node (ref "C17") (pin "1") (pinfunction "1_1") (pintype "passive"))
      (node (ref "C18") (pin "1") (pinfunction "1_1") (pintype "passive"))
      (node (ref "C4") (pin "2") (pinfunction "2_2") (pintype "passive"))
      (node (ref "C6") (pin "1") (pinfunction "1_1") (pintype "passive"))
      (node (ref "C7") (pin "1") (pinfunction "1_1") (pintype "passive"))
      (node (ref "FCM1608") (pin "1") (pinfunction "P$1_1") (pintype "bidirectional"))
      (node (ref "I2C") (pin "3") (pinfunction "3_3") (pintype "passive"))
      (node (ref "NRF24L01_SMD") (pin "P$8") (pinfunction "VDD_P$8") (pintype "bidirectional"))
      (node (ref "R11") (pin "1") (pinfunction "1_1") (pintype "passive"))
      (node (ref "R17") (pin "1") (pinfunction "1_1") (pintype "passive"))
      (node (ref "R20") (pin "2") (pinfunction "2_2") (pintype "passive"))
      (node (ref "R7") (pin "1") (pinfunction "1_1") (pintype "passive"))
      (node (ref "R9") (pin "1") (pinfunction "1_1") (pintype "passive"))
      (node (ref "REG1117") (pin "2") (pinfunction "VOUT_2") (pintype "power_in"))
      (node (ref "REG1117") (pin "4") (pinfunction "VOUT_4") (pintype "power_in"))
      (node (ref "STM32F103C8") (pin "1") (pinfunction "VBAT_1") (pintype "power_in"))
      (node (ref "STM32F103C8") (pin "24") (pinfunction "VDD_1_24") (pintype "power_in"))
      (node (ref "STM32F103C8") (pin "36") (pinfunction "VDD_2_36") (pintype "power_in"))
      (node (ref "STM32F103C8") (pin "48") (pinfunction "VDD_3_48") (pintype "power_in"))
      (node (ref "SWD") (pin "1") (pinfunction "1_1") (pintype "passive"))
    )
    (net (code "57") (name "VI") (class "Default")
      (node (ref "BAT60J") (pin "C") (pinfunction "C_C") (pintype "passive"))
      (node (ref "C10") (pin "1") (pinfunction "1_1") (pintype "passive"))
      (node (ref "C20") (pin "1") (pinfunction "1_1") (pintype "passive"))
      (node (ref "R13") (pin "2") (pinfunction "2_2") (pintype "passive"))
      (node (ref "R6") (pin "1") (pinfunction "1_1") (pintype "passive"))
      (node (ref "U1") (pin "1") (pinfunction "VI_1") (pintype "power_in"))
      (node (ref "USART") (pin "3") (pinfunction "3_3") (pintype "passive"))
    )
    (net (code "58") (name "unconnected-(STM32F103C8C-PA0-Pad10)") (class "Default")
      (node (ref "STM32F103C8") (pin "10") (pinfunction "PA0_10") (pintype "bidirectional"))
    )
    (net (code "59") (name "unconnected-(STM32F103C8D-PB12-Pad25)") (class "Default")
      (node (ref "STM32F103C8") (pin "25") (pinfunction "PB12_25") (pintype "bidirectional"))
    )
    (net (code "60") (name "unconnected-(STM32F103C8F-PC13-Pad2)") (class "Default")
      (node (ref "STM32F103C8") (pin "2") (pinfunction "PC13_2") (pintype "bidirectional"))
    )
    (net (code "61") (name "unconnected-(STM32F103C8F-PC14-Pad3)") (class "Default")
      (node (ref "STM32F103C8") (pin "3") (pinfunction "PC14_3") (pintype "bidirectional"))
    )
    (net (code "62") (name "unconnected-(STM32F103C8F-PC15-Pad4)") (class "Default")
      (node (ref "STM32F103C8") (pin "4") (pinfunction "PC15_4") (pintype "bidirectional"))
    )
    (net (code "63") (name "unconnected-(U$1-PadGPIO_2)") (class "Default")
      (node (ref "U$1") (pin "GPIO_2") (pinfunction "GPIO_2_GPIO_2") (pintype "bidirectional"))
    )
    (net (code "64") (name "unconnected-(U$4-Pad1)") (class "Default")
      (node (ref "U$4") (pin "1") (pinfunction "1_1") (pintype "passive"))
    )
    (net (code "65") (name "unconnected-(U$4-Pad2)") (class "Default")
      (node (ref "U$4") (pin "2") (pinfunction "2_2") (pintype "passive"))
    )
    (net (code "66") (name "unconnected-(U$4-Pad3)") (class "Default")
      (node (ref "U$4") (pin "3") (pinfunction "3_3") (pintype "passive"))
    )
    (net (code "67") (name "unconnected-(U$4-Pad4)") (class "Default")
      (node (ref "U$4") (pin "4") (pinfunction "4_4") (pintype "passive"))
    )
    (net (code "68") (name "unconnected-(U$4-Pad5)") (class "Default")
      (node (ref "U$4") (pin "5") (pinfunction "5_5") (pintype "passive"))
    )
  )
)
